# 464342_21-005_3_5.net
KiCad netlist of a schematic drawn in Altium Designer
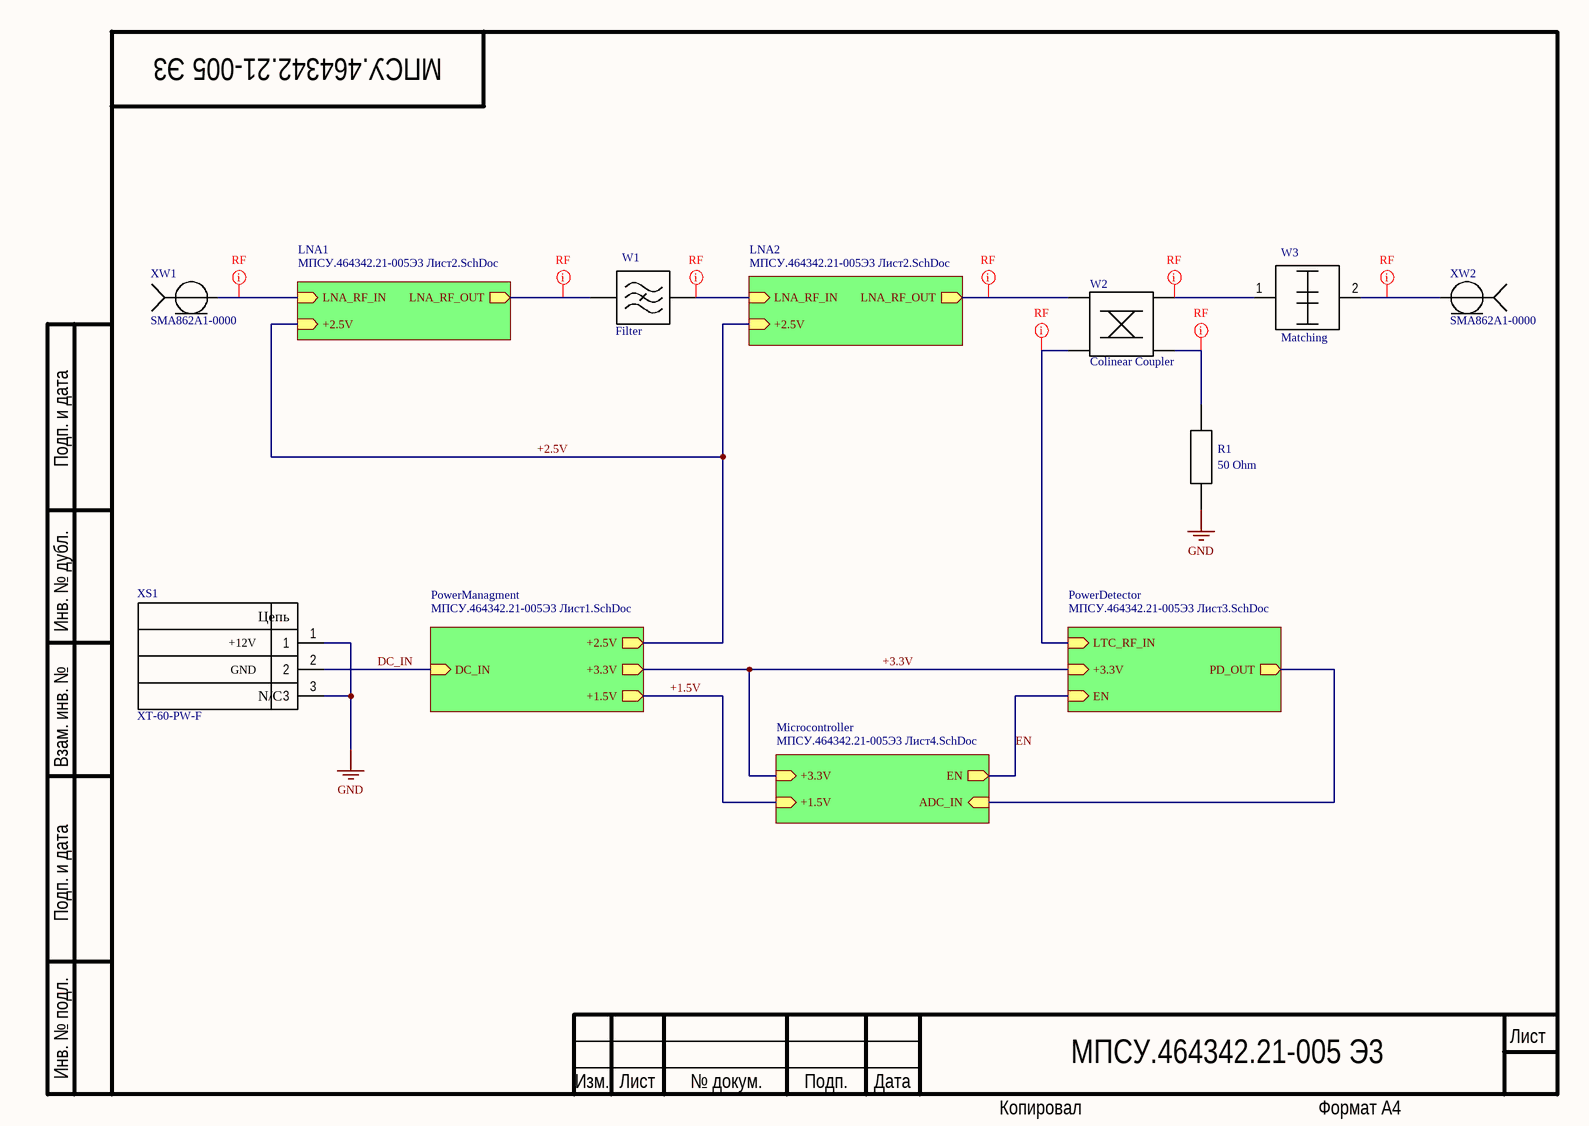
[diagram p0: МПСУ.464342.21-005Э3 Лист5.SchDoc]

(export (version "E")
  (design (tool "Eeschema 10.0.6"))
  (components
    (comp (ref "R1")
      (value "50 Ohm")
      (footprint "RESC160X80X60L30N")
      (description "Resistor, generic")
      (fields (field (name "POWER") "5 W"))
      (libsource (lib "Discrete") (part "Resistor"))
    )
    (comp (ref "W1")
      (value "Filter")
      (footprint "MFilter8_5G")
      (libsource (lib "Microstrip") (part "Filter 8.5G"))
    )
    (comp (ref "W2")
      (value "Colinear Coupler")
      (footprint "CLCoupler")
      (description "Coupler 40 dB, diel RO4003 0.5 oz ED 20 mil")
      (libsource (lib "Microstrip") (part "CLCoupler"))
    )
    (comp (ref "W3")
      (value "Matching")
      (footprint "MATCHING_MAIN_OUT")
      (libsource (lib "Microstrip") (part "Matching_1"))
    )
    (comp (ref "XS1")
      (value "XT-60-PW-F")
      (footprint "Connectors:XT-60-PW-F")
      (description "Header, Right-angle, 2x1")
      (fields (field (name "NET2") "GND") (field (name "NET1") "+12V"))
      (libsource (lib "Connectors") (part "XT-60-PW-F"))
    )
    (comp (ref "XW1")
      (value "SMA862A1-0000")
      (footprint "SMA862A1-0000")
      (description "SMA Jack For Panel Receptacle 50Ohm JYEBAO")
      (libsource (lib "Connectors") (part "SMA862A1-0000"))
    )
    (comp (ref "XW2")
      (value "SMA862A1-0000")
      (footprint "SMA862A1-0000")
      (description "SMA Jack For Panel Receptacle 50Ohm JYEBAO")
      (libsource (lib "Connectors") (part "SMA862A1-0000"))
    )
  )
  (nets
    (net (code "4") (name "/DC_IN") (class "Default")
      (node (ref "XS1") (pin "2") (pinfunction "2_2") (pintype "passive"))
    )
    (net (code "6") (name "/LNA_RF_IN") (class "Default")
      (node (ref "W1") (pin "2") (pinfunction "2_2") (pintype "passive"))
    )
    (net (code "7") (name "/LNA_RF_IN_1") (class "Default")
      (node (ref "XW1") (pin "1") (pinfunction "1_1") (pintype "passive"))
    )
    (net (code "8") (name "/LNA_RF_OUT") (class "Default")
      (node (ref "W2") (pin "1") (pinfunction "1_1") (pintype "passive"))
    )
    (net (code "9") (name "/LNA_RF_OUT_1") (class "Default")
      (node (ref "W1") (pin "1") (pinfunction "1_1") (pintype "passive"))
    )
    (net (code "10") (name "/LTC_RF_IN") (class "Default")
      (node (ref "W2") (pin "4") (pinfunction "4_4") (pintype "passive"))
    )
    (net (code "12") (name "GND") (class "Default")
      (node (ref "R1") (pin "1") (pinfunction "1_1") (pintype "passive"))
      (node (ref "XS1") (pin "1") (pinfunction "1_1") (pintype "passive"))
      (node (ref "XS1") (pin "3") (pinfunction "3_3") (pintype "passive"))
    )
    (net (code "13") (name "Net-(R1-Pad2)") (class "Default")
      (node (ref "R1") (pin "2") (pinfunction "2_2") (pintype "passive"))
      (node (ref "W2") (pin "3") (pinfunction "3_3") (pintype "passive"))
    )
    (net (code "14") (name "Net-(W2-Pad2)") (class "Default")
      (node (ref "W2") (pin "2") (pinfunction "2_2") (pintype "passive"))
      (node (ref "W3") (pin "1") (pinfunction "1_1") (pintype "passive"))
    )
    (net (code "15") (name "Net-(W3-Pad2)") (class "Default")
      (node (ref "W3") (pin "2") (pinfunction "2_2") (pintype "passive"))
      (node (ref "XW2") (pin "1") (pinfunction "1_1") (pintype "passive"))
    )
  )
)
